# M032.net
KiCad netlist of a schematic drawn in Altium Designer
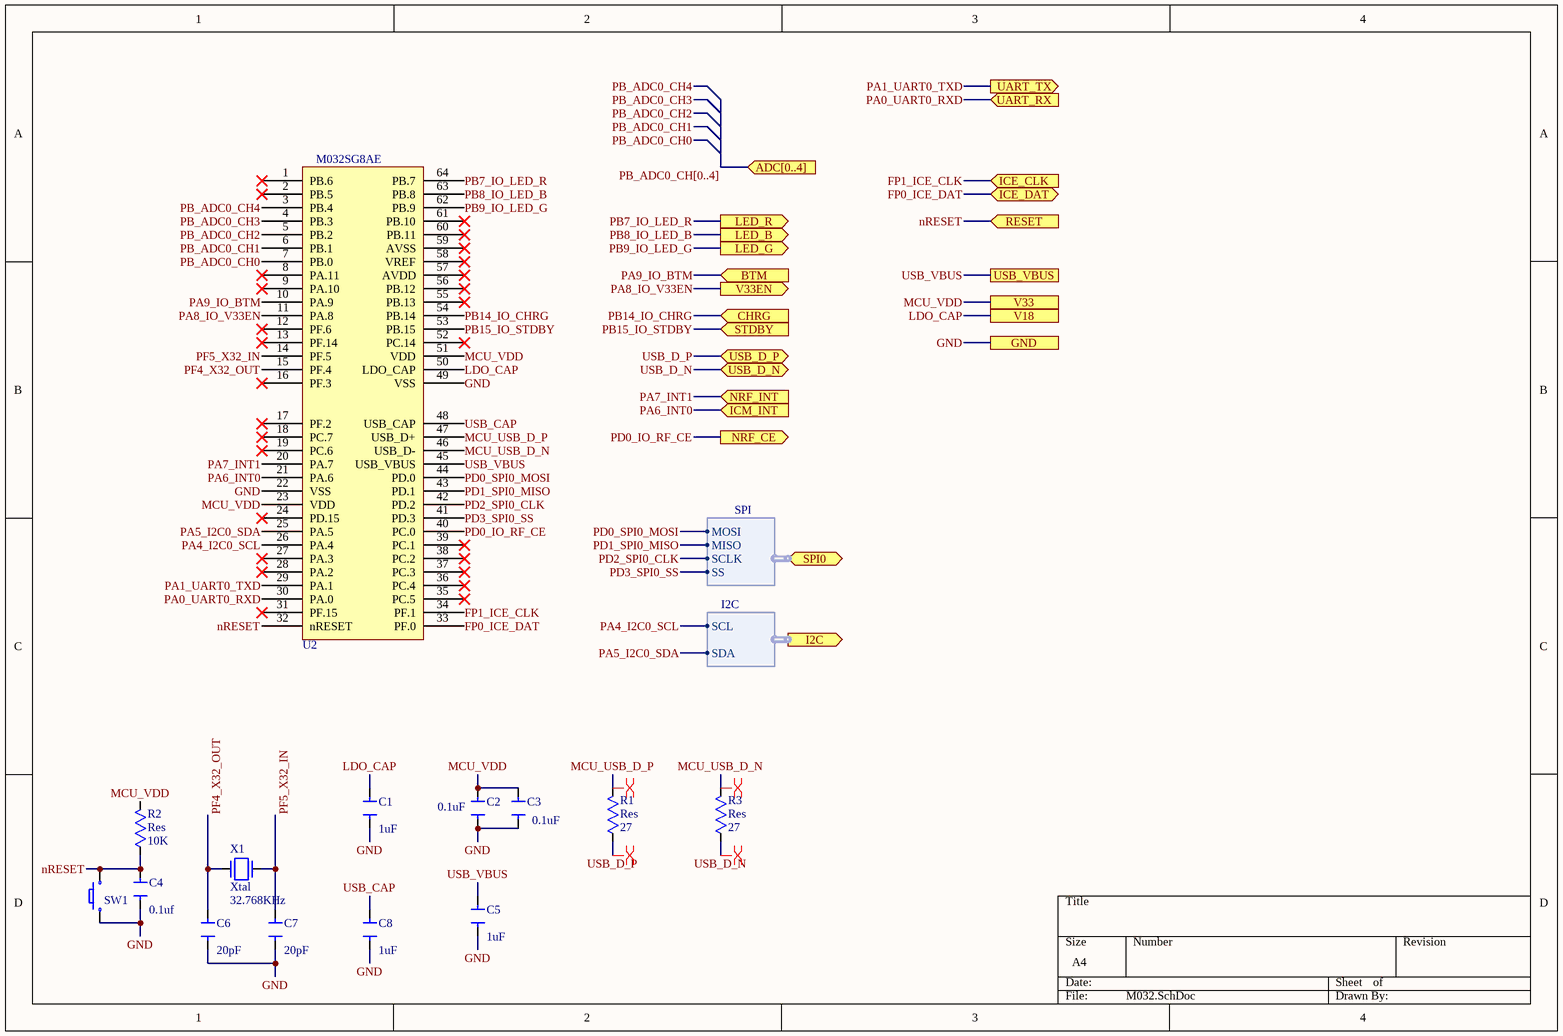
[diagram p0: M032.SchDoc]

(export (version "E")
  (design (tool "Eeschema 10.0.6"))
  (components
    (comp (ref "C1")
      (value "1uF")
      (footprint "CAP_0402")
      (fields (field (name "Comment") "Cap"))
      (libsource (lib "ZGR") (part "Cap"))
    )
    (comp (ref "C2")
      (value "0.1uF")
      (footprint "CAP_0402")
      (fields (field (name "Comment") "Cap"))
      (libsource (lib "ZGR") (part "Cap"))
    )
    (comp (ref "C3")
      (value "0.1uF")
      (footprint "CAP_0402")
      (fields (field (name "Comment") "Cap"))
      (libsource (lib "ZGR") (part "Cap"))
    )
    (comp (ref "C4")
      (value "0.1uf")
      (footprint "CAP_0402")
      (fields (field (name "Comment") "Cap"))
      (libsource (lib "ZGR") (part "Cap"))
    )
    (comp (ref "C5")
      (value "1uF")
      (footprint "CAP_0402")
      (fields (field (name "Comment") "Cap"))
      (libsource (lib "ZGR") (part "Cap"))
    )
    (comp (ref "C6")
      (value "20pF")
      (footprint "CAP_0402")
      (fields (field (name "Comment") "Cap"))
      (libsource (lib "ZGR") (part "Cap"))
    )
    (comp (ref "C7")
      (value "20pF")
      (footprint "CAP_0402")
      (fields (field (name "Comment") "Cap"))
      (libsource (lib "ZGR") (part "Cap"))
    )
    (comp (ref "C8")
      (value "1uF")
      (footprint "CAP_0402")
      (fields (field (name "Comment") "Cap"))
      (libsource (lib "ZGR") (part "Cap"))
    )
    (comp (ref "R1")
      (value "Res")
      (footprint "RES_0402")
      (fields (field (name "ALTIUM_VALUE") "27"))
      (libsource (lib "ZGR") (part "Res"))
    )
    (comp (ref "R2")
      (value "Res")
      (footprint "RES_0402")
      (fields (field (name "ALTIUM_VALUE") "10K"))
      (libsource (lib "ZGR") (part "Res"))
    )
    (comp (ref "R3")
      (value "Res")
      (footprint "RES_0402")
      (fields (field (name "ALTIUM_VALUE") "27"))
      (libsource (lib "ZGR") (part "Res"))
    )
    (comp (ref "SW1")
      (value "SPST")
      (footprint "TACK-SW_SMD 2P 4x3mm_2")
      (libsource (lib "ZGR") (part "Switch_Button1"))
    )
    (comp (ref "U2")
      (value "M032SG8AE")
      (footprint "MCU_LQFP_64_7x7")
      (libsource (lib "ZGR") (part "M032SG8AE"))
    )
    (comp (ref "X1")
      (value "Xtal")
      (footprint "X3215")
      (fields (field (name "ALTIUM_VALUE") "32.768KHz"))
      (libsource (lib "ZGR") (part "Xtal"))
    )
  )
  (nets
    (net (code "3") (name "/FP0_ICE_DAT") (class "Default")
      (node (ref "U2") (pin "33") (pinfunction "PF.0_33") (pintype "passive"))
    )
    (net (code "4") (name "/FP1_ICE_CLK") (class "Default")
      (node (ref "U2") (pin "34") (pinfunction "PF.1_34") (pintype "passive"))
    )
    (net (code "5") (name "/GND") (class "Default")
      (node (ref "C1") (pin "2") (pinfunction "2_2") (pintype "passive"))
      (node (ref "C2") (pin "2") (pinfunction "2_2") (pintype "passive"))
      (node (ref "C3") (pin "2") (pinfunction "2_2") (pintype "passive"))
      (node (ref "C4") (pin "2") (pinfunction "2_2") (pintype "passive"))
      (node (ref "C5") (pin "2") (pinfunction "2_2") (pintype "passive"))
      (node (ref "C6") (pin "2") (pinfunction "2_2") (pintype "passive"))
      (node (ref "C7") (pin "2") (pinfunction "2_2") (pintype "passive"))
      (node (ref "C8") (pin "2") (pinfunction "2_2") (pintype "passive"))
      (node (ref "SW1") (pin "2") (pinfunction "2_2") (pintype "passive"))
      (node (ref "U2") (pin "22") (pinfunction "VSS_22") (pintype "passive"))
      (node (ref "U2") (pin "49") (pinfunction "VSS_49") (pintype "passive"))
    )
    (net (code "6") (name "/LDO_CAP") (class "Default")
      (node (ref "C1") (pin "1") (pinfunction "1_1") (pintype "passive"))
      (node (ref "U2") (pin "50") (pinfunction "LDO_CAP_50") (pintype "passive"))
    )
    (net (code "7") (name "/MCU_USB_D_N") (class "Default")
      (node (ref "R3") (pin "1") (pinfunction "1_1") (pintype "passive"))
      (node (ref "U2") (pin "46") (pinfunction "USB_D-_46") (pintype "passive"))
    )
    (net (code "8") (name "/MCU_USB_D_P") (class "Default")
      (node (ref "R1") (pin "1") (pinfunction "1_1") (pintype "passive"))
      (node (ref "U2") (pin "47") (pinfunction "USB_D+_47") (pintype "passive"))
    )
    (net (code "9") (name "/MCU_VDD") (class "Default")
      (node (ref "C2") (pin "1") (pinfunction "1_1") (pintype "passive"))
      (node (ref "C3") (pin "1") (pinfunction "1_1") (pintype "passive"))
      (node (ref "R2") (pin "1") (pinfunction "1_1") (pintype "passive"))
      (node (ref "U2") (pin "23") (pinfunction "VDD_23") (pintype "passive"))
      (node (ref "U2") (pin "51") (pinfunction "VDD_51") (pintype "passive"))
    )
    (net (code "10") (name "/PA0_UART0_RXD") (class "Default")
      (node (ref "U2") (pin "30") (pinfunction "PA.0_30") (pintype "passive"))
    )
    (net (code "11") (name "/PA1_UART0_TXD") (class "Default")
      (node (ref "U2") (pin "29") (pinfunction "PA.1_29") (pintype "passive"))
    )
    (net (code "12") (name "/PA4_I2C0_SCL") (class "Default")
      (node (ref "U2") (pin "26") (pinfunction "PA.4_26") (pintype "passive"))
    )
    (net (code "13") (name "/PA5_I2C0_SDA") (class "Default")
      (node (ref "U2") (pin "25") (pinfunction "PA.5_25") (pintype "passive"))
    )
    (net (code "14") (name "/PA6_INT0") (class "Default")
      (node (ref "U2") (pin "21") (pinfunction "PA.6_21") (pintype "passive"))
    )
    (net (code "15") (name "/PA7_INT1") (class "Default")
      (node (ref "U2") (pin "20") (pinfunction "PA.7_20") (pintype "passive"))
    )
    (net (code "16") (name "/PA8_IO_V33EN") (class "Default")
      (node (ref "U2") (pin "11") (pinfunction "PA.8_11") (pintype "passive"))
    )
    (net (code "17") (name "/PA9_IO_BTM") (class "Default")
      (node (ref "U2") (pin "10") (pinfunction "PA.9_10") (pintype "passive"))
    )
    (net (code "18") (name "/PB7_IO_LED_R") (class "Default")
      (node (ref "U2") (pin "64") (pinfunction "PB.7_64") (pintype "passive"))
    )
    (net (code "19") (name "/PB8_IO_LED_B") (class "Default")
      (node (ref "U2") (pin "63") (pinfunction "PB.8_63") (pintype "passive"))
    )
    (net (code "20") (name "/PB9_IO_LED_G") (class "Default")
      (node (ref "U2") (pin "62") (pinfunction "PB.9_62") (pintype "passive"))
    )
    (net (code "21") (name "/PB14_IO_CHRG") (class "Default")
      (node (ref "U2") (pin "54") (pinfunction "PB.14_54") (pintype "passive"))
    )
    (net (code "22") (name "/PB15_IO_STDBY") (class "Default")
      (node (ref "U2") (pin "53") (pinfunction "PB.15_53") (pintype "passive"))
    )
    (net (code "23") (name "/PB_ADC0_CH0") (class "Default")
      (node (ref "U2") (pin "7") (pinfunction "PB.0_7") (pintype "passive"))
    )
    (net (code "24") (name "/PB_ADC0_CH1") (class "Default")
      (node (ref "U2") (pin "6") (pinfunction "PB.1_6") (pintype "passive"))
    )
    (net (code "25") (name "/PB_ADC0_CH2") (class "Default")
      (node (ref "U2") (pin "5") (pinfunction "PB.2_5") (pintype "passive"))
    )
    (net (code "26") (name "/PB_ADC0_CH3") (class "Default")
      (node (ref "U2") (pin "4") (pinfunction "PB.3_4") (pintype "passive"))
    )
    (net (code "27") (name "/PB_ADC0_CH4") (class "Default")
      (node (ref "U2") (pin "3") (pinfunction "PB.4_3") (pintype "passive"))
    )
    (net (code "29") (name "/PD0_IO_RF_CE") (class "Default")
      (node (ref "U2") (pin "40") (pinfunction "PC.0_40") (pintype "passive"))
    )
    (net (code "30") (name "/PD0_SPI0_MOSI") (class "Default")
      (node (ref "U2") (pin "44") (pinfunction "PD.0_44") (pintype "passive"))
    )
    (net (code "31") (name "/PD1_SPI0_MISO") (class "Default")
      (node (ref "U2") (pin "43") (pinfunction "PD.1_43") (pintype "passive"))
    )
    (net (code "32") (name "/PD2_SPI0_CLK") (class "Default")
      (node (ref "U2") (pin "42") (pinfunction "PD.2_42") (pintype "passive"))
    )
    (net (code "33") (name "/PD3_SPI0_SS") (class "Default")
      (node (ref "U2") (pin "41") (pinfunction "PD.3_41") (pintype "passive"))
    )
    (net (code "34") (name "/PF4_X32_OUT") (class "Default")
      (node (ref "C6") (pin "1") (pinfunction "1_1") (pintype "passive"))
      (node (ref "U2") (pin "15") (pinfunction "PF.4_15") (pintype "passive"))
      (node (ref "X1") (pin "2") (pintype "passive"))
    )
    (net (code "35") (name "/PF5_X32_IN") (class "Default")
      (node (ref "C7") (pin "1") (pinfunction "1_1") (pintype "passive"))
      (node (ref "U2") (pin "14") (pinfunction "PF.5_14") (pintype "passive"))
      (node (ref "X1") (pin "1") (pintype "passive"))
    )
    (net (code "36") (name "/USB_CAP") (class "Default")
      (node (ref "C8") (pin "1") (pinfunction "1_1") (pintype "passive"))
      (node (ref "U2") (pin "48") (pinfunction "USB_CAP_48") (pintype "passive"))
    )
    (net (code "37") (name "/USB_D_N") (class "Default")
      (node (ref "R3") (pin "2") (pinfunction "2_2") (pintype "passive"))
    )
    (net (code "38") (name "/USB_D_P") (class "Default")
      (node (ref "R1") (pin "2") (pinfunction "2_2") (pintype "passive"))
    )
    (net (code "39") (name "/USB_VBUS") (class "Default")
      (node (ref "C5") (pin "1") (pinfunction "1_1") (pintype "passive"))
      (node (ref "U2") (pin "45") (pinfunction "USB_VBUS_45") (pintype "passive"))
    )
    (net (code "40") (name "/nRESET") (class "Default")
      (node (ref "C4") (pin "1") (pinfunction "1_1") (pintype "passive"))
      (node (ref "R2") (pin "2") (pinfunction "2_2") (pintype "passive"))
      (node (ref "SW1") (pin "1") (pinfunction "1_1") (pintype "passive"))
      (node (ref "U2") (pin "32") (pinfunction "nRESET_32") (pintype "passive"))
    )
    (net (code "43") (name "unconnected-(U2-AVDD-Pad57)") (class "Default")
      (node (ref "U2") (pin "57") (pinfunction "AVDD_57") (pintype "passive+no_connect"))
    )
    (net (code "44") (name "unconnected-(U2-AVSS-Pad59)") (class "Default")
      (node (ref "U2") (pin "59") (pinfunction "AVSS_59") (pintype "passive+no_connect"))
    )
    (net (code "45") (name "unconnected-(U2-PA.2-Pad28)") (class "Default")
      (node (ref "U2") (pin "28") (pinfunction "PA.2_28") (pintype "passive+no_connect"))
    )
    (net (code "46") (name "unconnected-(U2-PA.3-Pad27)") (class "Default")
      (node (ref "U2") (pin "27") (pinfunction "PA.3_27") (pintype "passive+no_connect"))
    )
    (net (code "47") (name "unconnected-(U2-PA.10-Pad9)") (class "Default")
      (node (ref "U2") (pin "9") (pinfunction "PA.10_9") (pintype "passive+no_connect"))
    )
    (net (code "48") (name "unconnected-(U2-PA.11-Pad8)") (class "Default")
      (node (ref "U2") (pin "8") (pinfunction "PA.11_8") (pintype "passive+no_connect"))
    )
    (net (code "49") (name "unconnected-(U2-PB.5-Pad2)") (class "Default")
      (node (ref "U2") (pin "2") (pinfunction "PB.5_2") (pintype "passive+no_connect"))
    )
    (net (code "50") (name "unconnected-(U2-PB.6-Pad1)") (class "Default")
      (node (ref "U2") (pin "1") (pinfunction "PB.6_1") (pintype "passive+no_connect"))
    )
    (net (code "51") (name "unconnected-(U2-PB.10-Pad61)") (class "Default")
      (node (ref "U2") (pin "61") (pinfunction "PB.10_61") (pintype "passive+no_connect"))
    )
    (net (code "52") (name "unconnected-(U2-PB.11-Pad60)") (class "Default")
      (node (ref "U2") (pin "60") (pinfunction "PB.11_60") (pintype "passive+no_connect"))
    )
    (net (code "53") (name "unconnected-(U2-PB.12-Pad56)") (class "Default")
      (node (ref "U2") (pin "56") (pinfunction "PB.12_56") (pintype "passive+no_connect"))
    )
    (net (code "54") (name "unconnected-(U2-PB.13-Pad55)") (class "Default")
      (node (ref "U2") (pin "55") (pinfunction "PB.13_55") (pintype "passive+no_connect"))
    )
    (net (code "55") (name "unconnected-(U2-PC.1-Pad39)") (class "Default")
      (node (ref "U2") (pin "39") (pinfunction "PC.1_39") (pintype "passive+no_connect"))
    )
    (net (code "56") (name "unconnected-(U2-PC.2-Pad38)") (class "Default")
      (node (ref "U2") (pin "38") (pinfunction "PC.2_38") (pintype "passive+no_connect"))
    )
    (net (code "57") (name "unconnected-(U2-PC.3-Pad37)") (class "Default")
      (node (ref "U2") (pin "37") (pinfunction "PC.3_37") (pintype "passive+no_connect"))
    )
    (net (code "58") (name "unconnected-(U2-PC.4-Pad36)") (class "Default")
      (node (ref "U2") (pin "36") (pinfunction "PC.4_36") (pintype "passive+no_connect"))
    )
    (net (code "59") (name "unconnected-(U2-PC.5-Pad35)") (class "Default")
      (node (ref "U2") (pin "35") (pinfunction "PC.5_35") (pintype "passive+no_connect"))
    )
    (net (code "60") (name "unconnected-(U2-PC.6-Pad19)") (class "Default")
      (node (ref "U2") (pin "19") (pinfunction "PC.6_19") (pintype "passive+no_connect"))
    )
    (net (code "61") (name "unconnected-(U2-PC.7-Pad18)") (class "Default")
      (node (ref "U2") (pin "18") (pinfunction "PC.7_18") (pintype "passive+no_connect"))
    )
    (net (code "62") (name "unconnected-(U2-PC.14-Pad52)") (class "Default")
      (node (ref "U2") (pin "52") (pinfunction "PC.14_52") (pintype "passive+no_connect"))
    )
    (net (code "63") (name "unconnected-(U2-PD.15-Pad24)") (class "Default")
      (node (ref "U2") (pin "24") (pinfunction "PD.15_24") (pintype "passive+no_connect"))
    )
    (net (code "64") (name "unconnected-(U2-PF.2-Pad17)") (class "Default")
      (node (ref "U2") (pin "17") (pinfunction "PF.2_17") (pintype "passive+no_connect"))
    )
    (net (code "65") (name "unconnected-(U2-PF.3-Pad16)") (class "Default")
      (node (ref "U2") (pin "16") (pinfunction "PF.3_16") (pintype "passive+no_connect"))
    )
    (net (code "66") (name "unconnected-(U2-PF.6-Pad12)") (class "Default")
      (node (ref "U2") (pin "12") (pinfunction "PF.6_12") (pintype "passive+no_connect"))
    )
    (net (code "67") (name "unconnected-(U2-PF.14-Pad13)") (class "Default")
      (node (ref "U2") (pin "13") (pinfunction "PF.14_13") (pintype "passive+no_connect"))
    )
    (net (code "68") (name "unconnected-(U2-PF.15-Pad31)") (class "Default")
      (node (ref "U2") (pin "31") (pinfunction "PF.15_31") (pintype "passive+no_connect"))
    )
    (net (code "69") (name "unconnected-(U2-VREF-Pad58)") (class "Default")
      (node (ref "U2") (pin "58") (pinfunction "VREF_58") (pintype "passive+no_connect"))
    )
  )
)
